# buffmult-rev2.net
KiCad netlist of a schematic drawn in EAGLE
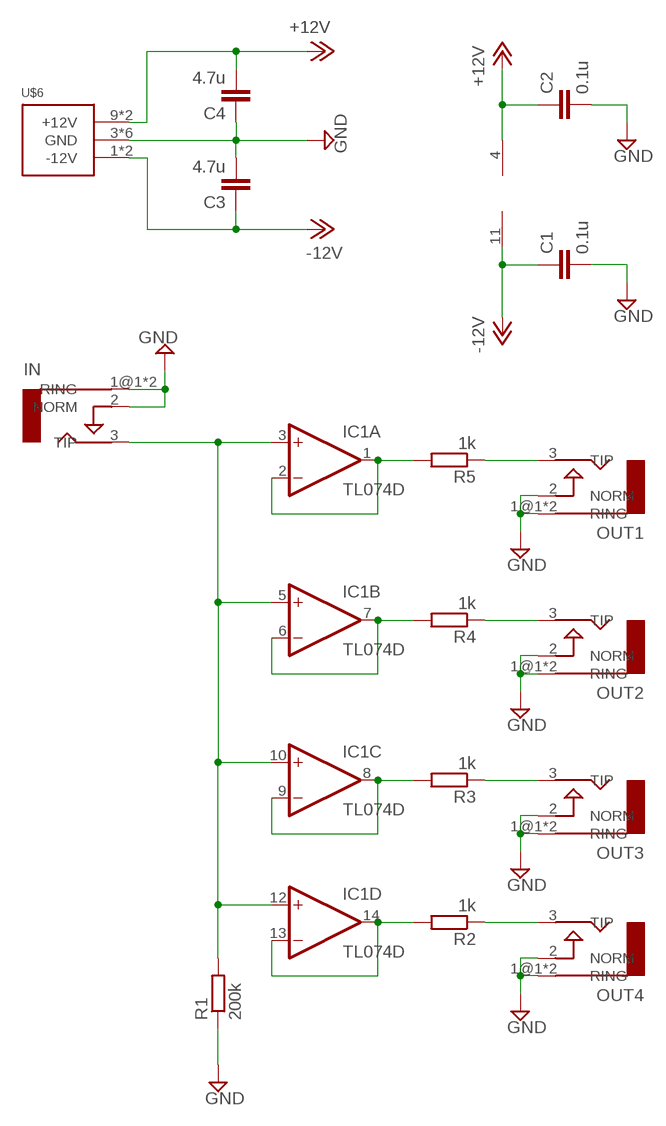
[diagram p0: schematic, sheet 1]

(export (version "E")
  (design (tool "Eeschema 10.0.6"))
  (components
    (comp (ref "C1")
      (value "0.1u")
      (footprint "eagle-import:C0805")
      (libsource (lib "eagle-import") (part "C-EUC0805"))
    )
    (comp (ref "C2")
      (value "0.1u")
      (footprint "eagle-import:C0805")
      (libsource (lib "eagle-import") (part "C-EUC0805"))
    )
    (comp (ref "C3")
      (value "4.7u")
      (footprint "eagle-import:C0805")
      (libsource (lib "eagle-import") (part "C-EUC0805"))
    )
    (comp (ref "C4")
      (value "4.7u")
      (footprint "eagle-import:C0805")
      (libsource (lib "eagle-import") (part "C-EUC0805"))
    )
    (comp (ref "IC1")
      (value "TL074D")
      (footprint "eagle-import:SO14")
      (libsource (lib "eagle-import") (part "TL074D"))
    )
    (comp (ref "IN")
      (value "AUDIO-JACKERTHENVAR")
      (footprint "eagle-import:ERTHENVAR-JACK")
      (libsource (lib "eagle-import") (part "AUDIO-JACKERTHENVAR"))
    )
    (comp (ref "OUT1")
      (value "AUDIO-JACKERTHENVAR")
      (footprint "eagle-import:ERTHENVAR-JACK")
      (libsource (lib "eagle-import") (part "AUDIO-JACKERTHENVAR"))
    )
    (comp (ref "OUT2")
      (value "AUDIO-JACKERTHENVAR")
      (footprint "eagle-import:ERTHENVAR-JACK")
      (libsource (lib "eagle-import") (part "AUDIO-JACKERTHENVAR"))
    )
    (comp (ref "OUT3")
      (value "AUDIO-JACKERTHENVAR")
      (footprint "eagle-import:ERTHENVAR-JACK")
      (libsource (lib "eagle-import") (part "AUDIO-JACKERTHENVAR"))
    )
    (comp (ref "OUT4")
      (value "AUDIO-JACKERTHENVAR")
      (footprint "eagle-import:ERTHENVAR-JACK")
      (libsource (lib "eagle-import") (part "AUDIO-JACKERTHENVAR"))
    )
    (comp (ref "R1")
      (value "200k")
      (footprint "eagle-import:R0805")
      (libsource (lib "eagle-import") (part "R-EU_R0805"))
    )
    (comp (ref "R2")
      (value "1k")
      (footprint "eagle-import:R0805")
      (libsource (lib "eagle-import") (part "R-EU_R0805"))
    )
    (comp (ref "R3")
      (value "1k")
      (footprint "eagle-import:R0805")
      (libsource (lib "eagle-import") (part "R-EU_R0805"))
    )
    (comp (ref "R4")
      (value "1k")
      (footprint "eagle-import:R0805")
      (libsource (lib "eagle-import") (part "R-EU_R0805"))
    )
    (comp (ref "R5")
      (value "1k")
      (footprint "eagle-import:R0805")
      (libsource (lib "eagle-import") (part "R-EU_R0805"))
    )
    (comp (ref "U$6")
      (value "POWER_SIMPLE10")
      (footprint "eagle-import:POWER_10")
      (libsource (lib "eagle-import") (part "POWER_SIMPLE10"))
    )
  )
  (nets
    (net (code "1") (name "+12V") (class "Default")
      (node (ref "C2") (pin "1") (pinfunction "1_1") (pintype "passive"))
      (node (ref "C4") (pin "2") (pinfunction "2_2") (pintype "passive"))
      (node (ref "IC1") (pin "4") (pinfunction "V+_4") (pintype "power_in"))
      (node (ref "U$6") (pin "10") (pinfunction "+12V_10") (pintype "bidirectional"))
      (node (ref "U$6") (pin "9") (pinfunction "+12V_9") (pintype "bidirectional"))
    )
    (net (code "2") (name "-12V") (class "Default")
      (node (ref "C1") (pin "1") (pinfunction "1_1") (pintype "passive"))
      (node (ref "C3") (pin "1") (pinfunction "1_1") (pintype "passive"))
      (node (ref "IC1") (pin "11") (pinfunction "V-_11") (pintype "power_in"))
      (node (ref "U$6") (pin "1") (pinfunction "-12V_1") (pintype "bidirectional"))
      (node (ref "U$6") (pin "2") (pinfunction "-12V_2") (pintype "bidirectional"))
    )
    (net (code "3") (name "GND") (class "Default")
      (node (ref "C1") (pin "2") (pinfunction "2_2") (pintype "passive"))
      (node (ref "C2") (pin "2") (pinfunction "2_2") (pintype "passive"))
      (node (ref "C3") (pin "2") (pinfunction "2_2") (pintype "passive"))
      (node (ref "C4") (pin "1") (pinfunction "1_1") (pintype "passive"))
      (node (ref "IN") (pin "1@1") (pinfunction "RING_1@1") (pintype "bidirectional"))
      (node (ref "IN") (pin "1@2") (pinfunction "RING_1@2") (pintype "bidirectional"))
      (node (ref "IN") (pin "2") (pinfunction "NORM_2") (pintype "bidirectional"))
      (node (ref "OUT1") (pin "1@1") (pinfunction "RING_1@1") (pintype "bidirectional"))
      (node (ref "OUT1") (pin "1@2") (pinfunction "RING_1@2") (pintype "bidirectional"))
      (node (ref "OUT1") (pin "2") (pinfunction "NORM_2") (pintype "bidirectional"))
      (node (ref "OUT2") (pin "1@1") (pinfunction "RING_1@1") (pintype "bidirectional"))
      (node (ref "OUT2") (pin "1@2") (pinfunction "RING_1@2") (pintype "bidirectional"))
      (node (ref "OUT2") (pin "2") (pinfunction "NORM_2") (pintype "bidirectional"))
      (node (ref "OUT3") (pin "1@1") (pinfunction "RING_1@1") (pintype "bidirectional"))
      (node (ref "OUT3") (pin "1@2") (pinfunction "RING_1@2") (pintype "bidirectional"))
      (node (ref "OUT3") (pin "2") (pinfunction "NORM_2") (pintype "bidirectional"))
      (node (ref "OUT4") (pin "1@1") (pinfunction "RING_1@1") (pintype "bidirectional"))
      (node (ref "OUT4") (pin "1@2") (pinfunction "RING_1@2") (pintype "bidirectional"))
      (node (ref "OUT4") (pin "2") (pinfunction "NORM_2") (pintype "bidirectional"))
      (node (ref "R1") (pin "1") (pinfunction "1_1") (pintype "passive"))
      (node (ref "U$6") (pin "3") (pinfunction "GND_3") (pintype "bidirectional"))
      (node (ref "U$6") (pin "4") (pinfunction "GND_4") (pintype "bidirectional"))
      (node (ref "U$6") (pin "5") (pinfunction "GND_5") (pintype "bidirectional"))
      (node (ref "U$6") (pin "6") (pinfunction "GND_6") (pintype "bidirectional"))
      (node (ref "U$6") (pin "7") (pinfunction "GND_7") (pintype "bidirectional"))
      (node (ref "U$6") (pin "8") (pinfunction "GND_8") (pintype "bidirectional"))
    )
    (net (code "4") (name "Net-(IC1A-+IN)") (class "Default")
      (node (ref "IC1") (pin "10") (pinfunction "+IN_10") (pintype "input"))
      (node (ref "IC1") (pin "12") (pinfunction "+IN_12") (pintype "input"))
      (node (ref "IC1") (pin "3") (pinfunction "+IN_3") (pintype "input"))
      (node (ref "IC1") (pin "5") (pinfunction "+IN_5") (pintype "input"))
      (node (ref "IN") (pin "3") (pinfunction "TIP_3") (pintype "bidirectional"))
      (node (ref "R1") (pin "2") (pinfunction "2_2") (pintype "passive"))
    )
    (net (code "5") (name "Net-(IC1A--IN)") (class "Default")
      (node (ref "IC1") (pin "1") (pinfunction "OUT_1") (pintype "output"))
      (node (ref "IC1") (pin "2") (pinfunction "-IN_2") (pintype "input"))
      (node (ref "R5") (pin "2") (pinfunction "2_2") (pintype "passive"))
    )
    (net (code "6") (name "Net-(IC1B--IN)") (class "Default")
      (node (ref "IC1") (pin "6") (pinfunction "-IN_6") (pintype "input"))
      (node (ref "IC1") (pin "7") (pinfunction "OUT_7") (pintype "output"))
      (node (ref "R4") (pin "2") (pinfunction "2_2") (pintype "passive"))
    )
    (net (code "7") (name "Net-(IC1C--IN)") (class "Default")
      (node (ref "IC1") (pin "8") (pinfunction "OUT_8") (pintype "output"))
      (node (ref "IC1") (pin "9") (pinfunction "-IN_9") (pintype "input"))
      (node (ref "R3") (pin "2") (pinfunction "2_2") (pintype "passive"))
    )
    (net (code "8") (name "Net-(IC1D--IN)") (class "Default")
      (node (ref "IC1") (pin "13") (pinfunction "-IN_13") (pintype "input"))
      (node (ref "IC1") (pin "14") (pinfunction "OUT_14") (pintype "output"))
      (node (ref "R2") (pin "2") (pinfunction "2_2") (pintype "passive"))
    )
    (net (code "9") (name "Net-(OUT1-TIP)") (class "Default")
      (node (ref "OUT1") (pin "3") (pinfunction "TIP_3") (pintype "bidirectional"))
      (node (ref "R5") (pin "1") (pinfunction "1_1") (pintype "passive"))
    )
    (net (code "10") (name "Net-(OUT2-TIP)") (class "Default")
      (node (ref "OUT2") (pin "3") (pinfunction "TIP_3") (pintype "bidirectional"))
      (node (ref "R4") (pin "1") (pinfunction "1_1") (pintype "passive"))
    )
    (net (code "11") (name "Net-(OUT3-TIP)") (class "Default")
      (node (ref "OUT3") (pin "3") (pinfunction "TIP_3") (pintype "bidirectional"))
      (node (ref "R3") (pin "1") (pinfunction "1_1") (pintype "passive"))
    )
    (net (code "12") (name "Net-(OUT4-TIP)") (class "Default")
      (node (ref "OUT4") (pin "3") (pinfunction "TIP_3") (pintype "bidirectional"))
      (node (ref "R2") (pin "1") (pinfunction "1_1") (pintype "passive"))
    )
  )
)
